# STM32.net
KiCad netlist of a schematic drawn in Altium Designer
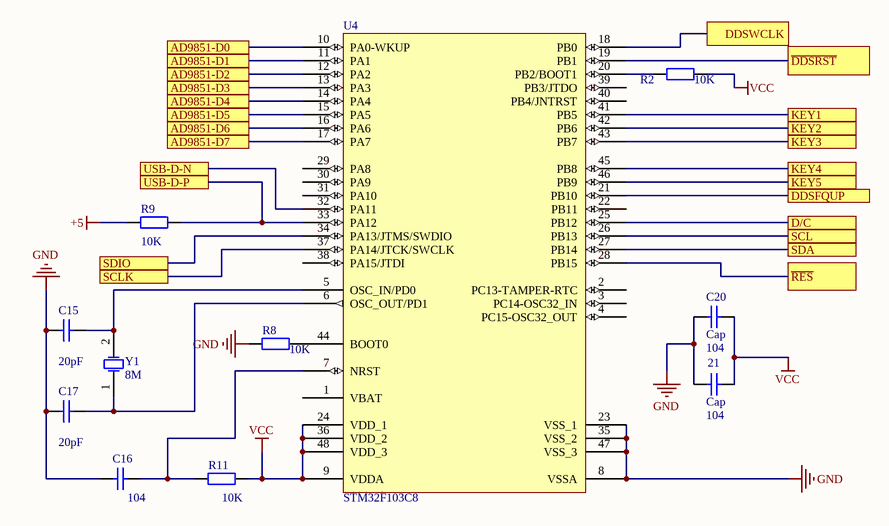
[diagram p0: STM32单片机最小系统.SchDoc]

(export (version "E")
  (design (tool "Eeschema 10.0.6"))
  (components
    (comp (ref "21")
      (value "Cap")
      (footprint "C0805")
      (description "Capacitor")
      (fields (field (name "ALTIUM_VALUE") "104") (field (name "PUBLISHER") "Altium Limited"))
      (libsource (lib "基于SMT32的DDS信号源原理图库") (part "Cap"))
    )
    (comp (ref "C15")
      (value "20pF")
      (footprint "C0805")
      (description "Capacitor")
      (fields (field (name "Comment") "Cap") (field (name "PUBLISHER") "Altium Limited"))
      (libsource (lib "基于SMT32的DDS信号源原理图库") (part "Cap"))
    )
    (comp (ref "C16")
      (value "104")
      (footprint "C0805")
      (description "Capacitor")
      (fields (field (name "Comment") "Cap") (field (name "PUBLISHER") "Altium Limited"))
      (libsource (lib "基于SMT32的DDS信号源原理图库") (part "Cap"))
    )
    (comp (ref "C17")
      (value "20pF")
      (footprint "C0805")
      (description "Capacitor")
      (fields (field (name "Comment") "Cap") (field (name "PUBLISHER") "Altium Limited"))
      (libsource (lib "基于SMT32的DDS信号源原理图库") (part "Cap"))
    )
    (comp (ref "C20")
      (value "Cap")
      (footprint "C0805")
      (description "Capacitor")
      (fields (field (name "ALTIUM_VALUE") "104") (field (name "PUBLISHER") "Altium Limited"))
      (libsource (lib "基于SMT32的DDS信号源原理图库") (part "Cap"))
    )
    (comp (ref "R2")
      (value "10K")
      (footprint "6-0805_N")
      (description "Resistor")
      (fields (field (name "Comment") "Res2") (field (name "PUBLISHER") "Altium Limited"))
      (libsource (lib "") (part "Res2_1"))
    )
    (comp (ref "R8")
      (value "10K")
      (footprint "6-0805_N")
      (description "Resistor")
      (fields (field (name "Comment") "Res2") (field (name "PUBLISHER") "Altium Limited"))
      (libsource (lib "Miscellaneous Devices") (part "Res2"))
    )
    (comp (ref "R9")
      (value "10K")
      (footprint "6-0805_N")
      (description "Resistor")
      (fields (field (name "Comment") "10k") (field (name "PUBLISHER") "Altium Limited"))
      (libsource (lib "") (part "Res2_1"))
    )
    (comp (ref "R11")
      (value "10K")
      (footprint "6-0805_N")
      (description "Resistor")
      (fields (field (name "Comment") "Res2") (field (name "PUBLISHER") "Altium Limited"))
      (libsource (lib "基于SMT32的DDS信号源原理图库") (part "Res2"))
    )
    (comp (ref "U4")
      (value "STM32F103C8")
      (footprint "TQFP-48")
      (description "Flaah:64/RAM:20/IO:36")
      (fields (field (name "版权归属") "源创客"))
      (libsource (lib "基于SMT32的DDS信号源原理图库") (part "STM32F103C8"))
    )
    (comp (ref "Y1")
      (value "8M")
      (footprint "XTAL2")
      (description "Crystal Oscillator")
      (fields (field (name "PUBLISHER") "Altium Limited"))
      (libsource (lib "基于SMT32的DDS信号源原理图库") (part "XTAL"))
    )
  )
  (nets
    (net (code "1") (name "+5") (class "Default")
      (node (ref "R9") (pin "2") (pinfunction "2_2") (pintype "passive"))
    )
    (net (code "2") (name "/AD9851-D0") (class "Default")
      (node (ref "U4") (pin "10") (pinfunction "PA0-WKUP_10") (pintype "bidirectional"))
    )
    (net (code "3") (name "/AD9851-D1") (class "Default")
      (node (ref "U4") (pin "11") (pinfunction "PA1_11") (pintype "bidirectional"))
    )
    (net (code "4") (name "/AD9851-D2") (class "Default")
      (node (ref "U4") (pin "12") (pinfunction "PA2_12") (pintype "bidirectional"))
    )
    (net (code "5") (name "/AD9851-D3") (class "Default")
      (node (ref "U4") (pin "13") (pinfunction "PA3_13") (pintype "bidirectional"))
    )
    (net (code "6") (name "/AD9851-D4") (class "Default")
      (node (ref "U4") (pin "14") (pinfunction "PA4_14") (pintype "bidirectional"))
    )
    (net (code "7") (name "/AD9851-D5") (class "Default")
      (node (ref "U4") (pin "15") (pinfunction "PA5_15") (pintype "bidirectional"))
    )
    (net (code "8") (name "/AD9851-D6") (class "Default")
      (node (ref "U4") (pin "16") (pinfunction "PA6_16") (pintype "bidirectional"))
    )
    (net (code "9") (name "/AD9851-D7") (class "Default")
      (node (ref "U4") (pin "17") (pinfunction "PA7_17") (pintype "bidirectional"))
    )
    (net (code "10") (name "/DDSFQUP") (class "Default")
      (node (ref "U4") (pin "21") (pinfunction "PB10_21") (pintype "bidirectional"))
    )
    (net (code "11") (name "/DDSWCLK") (class "Default")
      (node (ref "U4") (pin "18") (pinfunction "PB0_18") (pintype "bidirectional"))
    )
    (net (code "12") (name "/D{slash}C") (class "Default")
      (node (ref "U4") (pin "25") (pinfunction "PB12_25") (pintype "bidirectional"))
    )
    (net (code "13") (name "/KEY1") (class "Default")
      (node (ref "U4") (pin "41") (pinfunction "PB5_41") (pintype "bidirectional"))
    )
    (net (code "14") (name "/KEY2") (class "Default")
      (node (ref "U4") (pin "42") (pinfunction "PB6_42") (pintype "bidirectional"))
    )
    (net (code "15") (name "/KEY3") (class "Default")
      (node (ref "U4") (pin "43") (pinfunction "PB7_43") (pintype "bidirectional"))
    )
    (net (code "16") (name "/KEY4") (class "Default")
      (node (ref "U4") (pin "45") (pinfunction "PB8_45") (pintype "bidirectional"))
    )
    (net (code "17") (name "/KEY5") (class "Default")
      (node (ref "U4") (pin "46") (pinfunction "PB9_46") (pintype "bidirectional"))
    )
    (net (code "18") (name "/SCL") (class "Default")
      (node (ref "U4") (pin "26") (pinfunction "PB13_26") (pintype "bidirectional"))
    )
    (net (code "19") (name "/SCLK") (class "Default")
      (node (ref "U4") (pin "37") (pinfunction "PA14/JTCK/SWCLK_37") (pintype "bidirectional"))
    )
    (net (code "20") (name "/SDA") (class "Default")
      (node (ref "U4") (pin "27") (pinfunction "PB14_27") (pintype "bidirectional"))
    )
    (net (code "21") (name "/SDIO") (class "Default")
      (node (ref "U4") (pin "34") (pinfunction "PA13/JTMS/SWDIO_34") (pintype "bidirectional"))
    )
    (net (code "22") (name "/USB-D-N") (class "Default")
      (node (ref "U4") (pin "32") (pinfunction "PA11_32") (pintype "bidirectional"))
    )
    (net (code "23") (name "/USB-D-P") (class "Default")
      (node (ref "R9") (pin "1") (pinfunction "1_1") (pintype "passive"))
      (node (ref "U4") (pin "33") (pinfunction "PA12_33") (pintype "bidirectional"))
    )
    (net (code "24") (name "/~{DDSRST}") (class "Default")
      (node (ref "U4") (pin "19") (pinfunction "PB1_19") (pintype "bidirectional"))
    )
    (net (code "25") (name "/~{RES}") (class "Default")
      (node (ref "U4") (pin "28") (pinfunction "PB15_28") (pintype "bidirectional"))
    )
    (net (code "26") (name "GND") (class "Default")
      (node (ref "21") (pin "2") (pinfunction "2_2") (pintype "passive"))
      (node (ref "C15") (pin "2") (pinfunction "2_2") (pintype "passive"))
      (node (ref "C16") (pin "1") (pinfunction "1_1") (pintype "passive"))
      (node (ref "C17") (pin "2") (pinfunction "2_2") (pintype "passive"))
      (node (ref "C20") (pin "2") (pinfunction "2_2") (pintype "passive"))
      (node (ref "R8") (pin "2") (pinfunction "2_2") (pintype "passive"))
      (node (ref "U4") (pin "23") (pinfunction "VSS_1_23") (pintype "power_in"))
      (node (ref "U4") (pin "35") (pinfunction "VSS_2_35") (pintype "power_in"))
      (node (ref "U4") (pin "47") (pinfunction "VSS_3_47") (pintype "power_in"))
      (node (ref "U4") (pin "8") (pinfunction "VSSA_8") (pintype "power_in"))
    )
    (net (code "27") (name "Net-(U4-BOOT0)") (class "Default")
      (node (ref "R8") (pin "1") (pinfunction "1_1") (pintype "passive"))
      (node (ref "U4") (pin "44") (pinfunction "BOOT0_44") (pintype "passive"))
    )
    (net (code "28") (name "Net-(U4-NRST)") (class "Default")
      (node (ref "C16") (pin "2") (pinfunction "2_2") (pintype "passive"))
      (node (ref "R11") (pin "1") (pinfunction "1_1") (pintype "passive"))
      (node (ref "U4") (pin "7") (pinfunction "NRST_7") (pintype "bidirectional"))
    )
    (net (code "29") (name "Net-(U4-OSC_IN{slash}PD0)") (class "Default")
      (node (ref "C15") (pin "1") (pinfunction "1_1") (pintype "passive"))
      (node (ref "U4") (pin "5") (pinfunction "OSC_IN/PD0_5") (pintype "passive"))
      (node (ref "Y1") (pin "2") (pinfunction "OSC2_2") (pintype "passive"))
    )
    (net (code "30") (name "Net-(U4-OSC_OUT{slash}PD1)") (class "Default")
      (node (ref "C17") (pin "1") (pinfunction "1_1") (pintype "passive"))
      (node (ref "U4") (pin "6") (pinfunction "OSC_OUT/PD1_6") (pintype "output"))
      (node (ref "Y1") (pin "1") (pinfunction "OSC1_1") (pintype "passive"))
    )
    (net (code "31") (name "Net-(U4-PB2{slash}BOOT1)") (class "Default")
      (node (ref "R2") (pin "2") (pinfunction "2_2") (pintype "passive"))
      (node (ref "U4") (pin "20") (pinfunction "PB2/BOOT1_20") (pintype "bidirectional"))
    )
    (net (code "32") (name "VCC") (class "Default")
      (node (ref "21") (pin "1") (pinfunction "1_1") (pintype "passive"))
      (node (ref "C20") (pin "1") (pinfunction "1_1") (pintype "passive"))
      (node (ref "R11") (pin "2") (pinfunction "2_2") (pintype "passive"))
      (node (ref "R2") (pin "1") (pinfunction "1_1") (pintype "passive"))
      (node (ref "U4") (pin "24") (pinfunction "VDD_1_24") (pintype "power_in"))
      (node (ref "U4") (pin "36") (pinfunction "VDD_2_36") (pintype "power_in"))
      (node (ref "U4") (pin "48") (pinfunction "VDD_3_48") (pintype "power_in"))
      (node (ref "U4") (pin "9") (pinfunction "VDDA_9") (pintype "power_in"))
    )
    (net (code "33") (name "unconnected-(U4-PA8-Pad29)") (class "Default")
      (node (ref "U4") (pin "29") (pinfunction "PA8_29") (pintype "bidirectional"))
    )
    (net (code "34") (name "unconnected-(U4-PA9-Pad30)") (class "Default")
      (node (ref "U4") (pin "30") (pinfunction "PA9_30") (pintype "bidirectional"))
    )
    (net (code "35") (name "unconnected-(U4-PA10-Pad31)") (class "Default")
      (node (ref "U4") (pin "31") (pinfunction "PA10_31") (pintype "bidirectional"))
    )
    (net (code "36") (name "unconnected-(U4-PA15{slash}JTDI-Pad38)") (class "Default")
      (node (ref "U4") (pin "38") (pinfunction "PA15/JTDI_38") (pintype "bidirectional"))
    )
    (net (code "37") (name "unconnected-(U4-PB3{slash}JTDO-Pad39)") (class "Default")
      (node (ref "U4") (pin "39") (pinfunction "PB3/JTDO_39") (pintype "bidirectional"))
    )
    (net (code "38") (name "unconnected-(U4-PB4{slash}JNTRST-Pad40)") (class "Default")
      (node (ref "U4") (pin "40") (pinfunction "PB4/JNTRST_40") (pintype "bidirectional"))
    )
    (net (code "39") (name "unconnected-(U4-PB11-Pad22)") (class "Default")
      (node (ref "U4") (pin "22") (pinfunction "PB11_22") (pintype "bidirectional"))
    )
    (net (code "40") (name "unconnected-(U4-PC13-TAMPER-RTC-Pad2)") (class "Default")
      (node (ref "U4") (pin "2") (pinfunction "PC13-TAMPER-RTC_2") (pintype "bidirectional"))
    )
    (net (code "41") (name "unconnected-(U4-PC14-OSC32_IN-Pad3)") (class "Default")
      (node (ref "U4") (pin "3") (pinfunction "PC14-OSC32_IN_3") (pintype "bidirectional"))
    )
    (net (code "42") (name "unconnected-(U4-PC15-OSC32_OUT-Pad4)") (class "Default")
      (node (ref "U4") (pin "4") (pinfunction "PC15-OSC32_OUT_4") (pintype "bidirectional"))
    )
    (net (code "43") (name "unconnected-(U4-VBAT-Pad1)") (class "Default")
      (node (ref "U4") (pin "1") (pinfunction "VBAT_1") (pintype "power_in"))
    )
  )
)
